# diylinear1.net
KiCad netlist of a schematic drawn in EAGLE
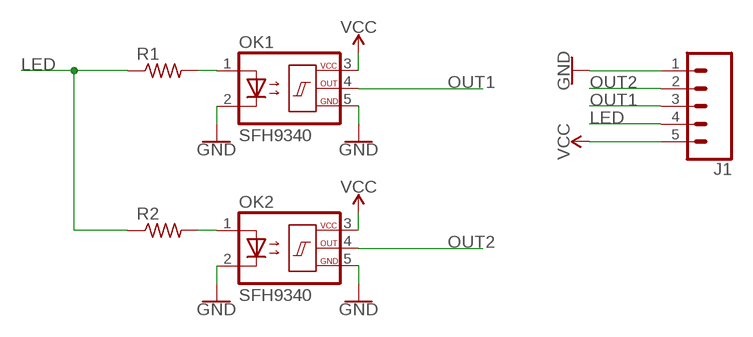
[diagram p0: schematic, sheet 1]

(export (version "E")
  (design (tool "Eeschema 10.0.6"))
  (components
    (comp (ref "J1")
      (value "CONN_05")
      (footprint "eagle-import:1X05")
      (libsource (lib "eagle-import") (part "CONN_05"))
    )
    (comp (ref "OK1")
      (value "SFH9340")
      (footprint "eagle-import:SFH9340")
      (libsource (lib "eagle-import") (part "SFH9340"))
    )
    (comp (ref "OK2")
      (value "SFH9340")
      (footprint "eagle-import:SFH9340")
      (libsource (lib "eagle-import") (part "SFH9340"))
    )
    (comp (ref "R1")
      (value "R-US_0204/5")
      (footprint "eagle-import:0204_5")
      (libsource (lib "eagle-import") (part "R-US_0204/5"))
    )
    (comp (ref "R2")
      (value "R-US_0204/5")
      (footprint "eagle-import:0204_5")
      (libsource (lib "eagle-import") (part "R-US_0204/5"))
    )
  )
  (nets
    (net (code "1") (name "/LED") (class "Default")
      (node (ref "J1") (pin "4") (pinfunction "4_4") (pintype "passive"))
      (node (ref "R1") (pin "1") (pinfunction "1_1") (pintype "passive"))
      (node (ref "R2") (pin "1") (pinfunction "1_1") (pintype "passive"))
    )
    (net (code "2") (name "/OUT1") (class "Default")
      (node (ref "J1") (pin "3") (pinfunction "3_3") (pintype "passive"))
      (node (ref "OK1") (pin "4") (pinfunction "OUT_4") (pintype "passive"))
    )
    (net (code "3") (name "/OUT2") (class "Default")
      (node (ref "J1") (pin "2") (pinfunction "2_2") (pintype "passive"))
      (node (ref "OK2") (pin "4") (pinfunction "OUT_4") (pintype "passive"))
    )
    (net (code "4") (name "GND") (class "Default")
      (node (ref "J1") (pin "1") (pinfunction "1_1") (pintype "passive"))
      (node (ref "OK1") (pin "2") (pinfunction "C_2") (pintype "passive"))
      (node (ref "OK1") (pin "5") (pinfunction "GND_5") (pintype "passive"))
      (node (ref "OK2") (pin "2") (pinfunction "C_2") (pintype "passive"))
      (node (ref "OK2") (pin "5") (pinfunction "GND_5") (pintype "passive"))
    )
    (net (code "5") (name "Net-(OK1-A)") (class "Default")
      (node (ref "OK1") (pin "1") (pinfunction "A_1") (pintype "passive"))
      (node (ref "R1") (pin "2") (pinfunction "2_2") (pintype "passive"))
    )
    (net (code "6") (name "Net-(OK2-A)") (class "Default")
      (node (ref "OK2") (pin "1") (pinfunction "A_1") (pintype "passive"))
      (node (ref "R2") (pin "2") (pinfunction "2_2") (pintype "passive"))
    )
    (net (code "7") (name "VCC") (class "Default")
      (node (ref "J1") (pin "5") (pinfunction "5_5") (pintype "passive"))
      (node (ref "OK1") (pin "3") (pinfunction "VCC_3") (pintype "passive"))
      (node (ref "OK2") (pin "3") (pinfunction "VCC_3") (pintype "passive"))
    )
  )
)
